# SEG_pressure_gauge_don_V2_3.net
KiCad netlist of a schematic drawn in Altium Designer
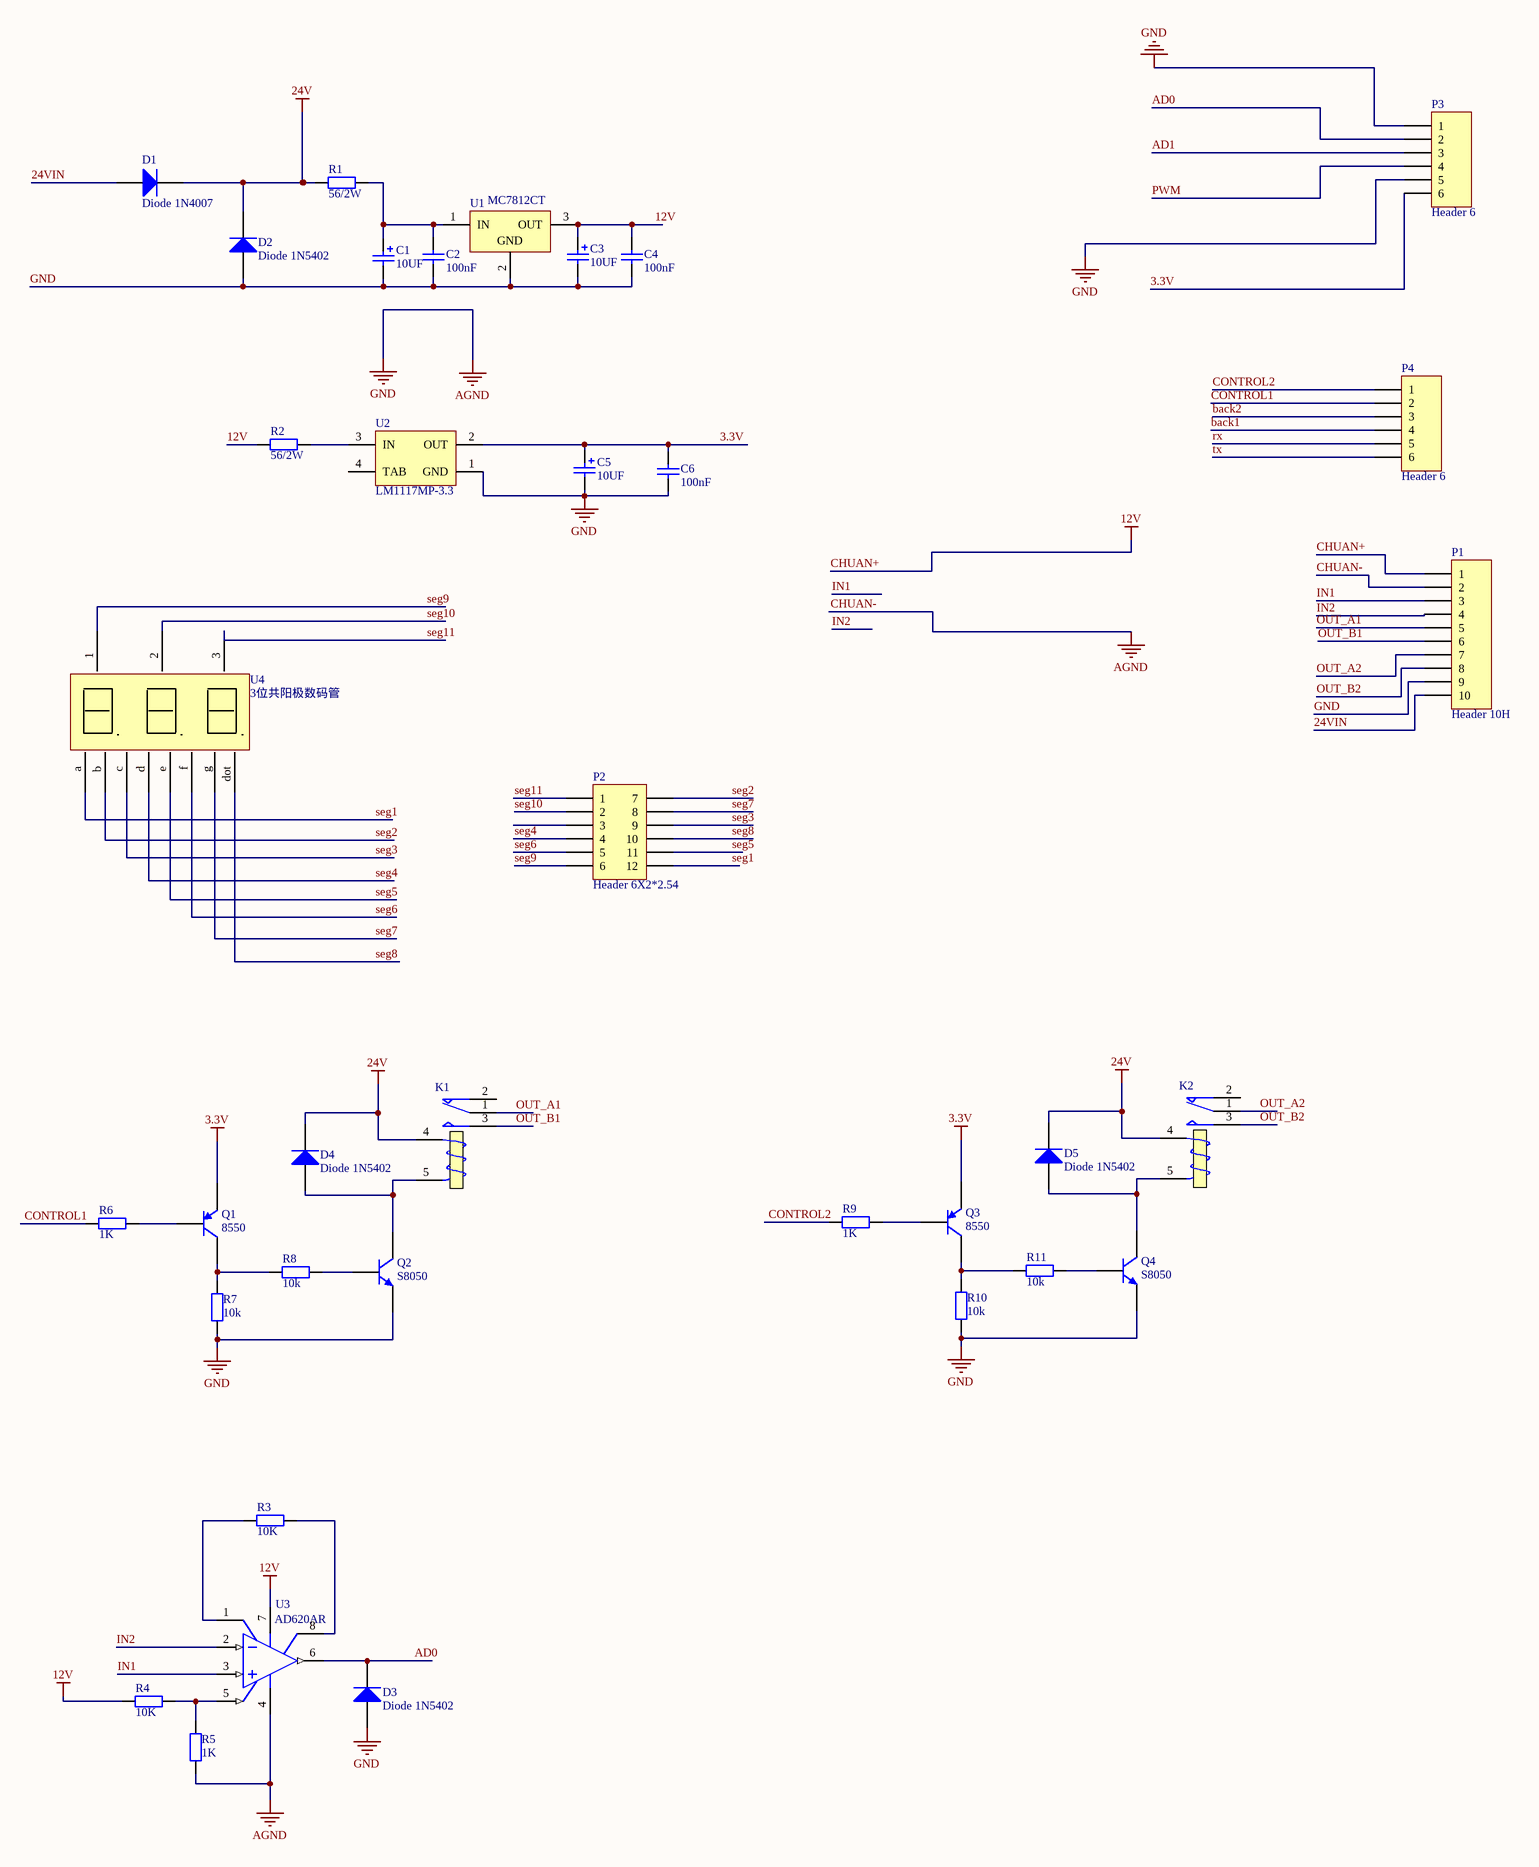
[diagram p0: SEG_pressure gauge_don  V2.3.SchDoc]

(export (version "E")
  (design (tool "Eeschema 10.0.6"))
  (components
    (comp (ref "C1")
      (value "10UF")
      (footprint "3216")
      (description "Polarized Capacitor (Axial)")
      (fields (field (name "Comment") "10uf") (field (name "PUBLISHER") "Altium Limited"))
      (libsource (lib "Miscellaneous Devices") (part "Cap Pol2"))
    )
    (comp (ref "C2")
      (value "100nF")
      (footprint "0805_C_Y")
      (description "Capacitor")
      (fields (field (name "Comment") "100nf") (field (name "PUBLISHER") "Altium Limited"))
      (libsource (lib "Miscellaneous Devices") (part "Cap"))
    )
    (comp (ref "C3")
      (value "10UF")
      (footprint "3216")
      (description "Polarized Capacitor (Axial)")
      (fields (field (name "Comment") "10uf") (field (name "PUBLISHER") "Altium Limited"))
      (libsource (lib "Miscellaneous Devices") (part "Cap Pol2"))
    )
    (comp (ref "C4")
      (value "100nF")
      (footprint "0805_C_Y")
      (description "Capacitor")
      (fields (field (name "Comment") "100nf") (field (name "PUBLISHER") "Altium Limited"))
      (libsource (lib "Miscellaneous Devices") (part "Cap"))
    )
    (comp (ref "C5")
      (value "10UF")
      (footprint "3216")
      (description "Polarized Capacitor (Axial)")
      (fields (field (name "Comment") "10uf") (field (name "PUBLISHER") "Altium Limited"))
      (libsource (lib "Miscellaneous Devices") (part "Cap Pol2"))
    )
    (comp (ref "C6")
      (value "100nF")
      (footprint "0805_C_Y")
      (description "Capacitor")
      (fields (field (name "Comment") "100nf") (field (name "PUBLISHER") "Altium Limited"))
      (libsource (lib "Miscellaneous Devices") (part "Cap"))
    )
    (comp (ref "D1")
      (value "Diode 1N4007")
      (footprint "DO-214")
      (description "1 Amp General Purpose Rectifier")
      (fields (field (name "PUBLISHER") "Altium Limited"))
      (libsource (lib "Miscellaneous Devices") (part "Diode 1N4007"))
    )
    (comp (ref "D2")
      (value "Diode 1N5402")
      (footprint "DO-214")
      (description "3 Amp General Purpose Rectifier")
      (fields (field (name "PUBLISHER") "Altium Limited"))
      (libsource (lib "Miscellaneous Devices") (part "Diode 1N5402"))
    )
    (comp (ref "D3")
      (value "Diode 1N5402")
      (footprint "DO-214")
      (description "3 Amp General Purpose Rectifier")
      (fields (field (name "PUBLISHER") "Altium Limited"))
      (libsource (lib "Miscellaneous Devices") (part "Diode 1N5402"))
    )
    (comp (ref "D4")
      (value "Diode 1N5402")
      (footprint "DO-214")
      (description "3 Amp General Purpose Rectifier")
      (fields (field (name "PUBLISHER") "Altium Limited"))
      (libsource (lib "Miscellaneous Devices") (part "Diode 1N5402"))
    )
    (comp (ref "D5")
      (value "Diode 1N5402")
      (footprint "DO-214")
      (description "3 Amp General Purpose Rectifier")
      (fields (field (name "PUBLISHER") "Altium Limited"))
      (libsource (lib "Miscellaneous Devices") (part "Diode 1N5402"))
    )
    (comp (ref "K1")
      (value "Relay")
      (footprint "HK4100F-DC24V-SHG??")
      (description "SPDT Relay")
      (fields (field (name "PUBLISHER") "Altium Limited"))
      (libsource (lib "Miscellaneous Devices") (part "Relay"))
    )
    (comp (ref "K2")
      (value "Relay")
      (footprint "HK4100F-DC24V-SHG??")
      (description "SPDT Relay")
      (fields (field (name "PUBLISHER") "Altium Limited"))
      (libsource (lib "Miscellaneous Devices") (part "Relay"))
    )
    (comp (ref "P1")
      (value "Header 10H")
      (footprint "HDR1X10H")
      (description "Header, 10-Pin, Right Angle")
      (fields (field (name "PUBLISHER") "Altium Limited"))
      (libsource (lib "Miscellaneous Connectors") (part "Header 10H"))
    )
    (comp (ref "P2")
      (value "Header 6X2*2.54")
      (footprint "HDR2X6_CEN")
      (description "Header, 6-Pin, Dual row")
      (fields (field (name "PUBLISHER") "Altium Limited"))
      (libsource (lib "Miscellaneous Connectors") (part "Header 6X2A"))
    )
    (comp (ref "P3")
      (value "Header 6")
      (footprint "HDR1X6")
      (description "Header, 6-Pin")
      (fields (field (name "PUBLISHER") "Altium Limited"))
      (libsource (lib "Miscellaneous Connectors") (part "Header 6"))
    )
    (comp (ref "P4")
      (value "Header 6")
      (footprint "HDR1X6")
      (description "Header, 6-Pin")
      (fields (field (name "PUBLISHER") "Altium Limited"))
      (libsource (lib "Miscellaneous Connectors") (part "Header 6"))
    )
    (comp (ref "Q1")
      (value "8550")
      (footprint "SOT-23_Y")
      (description "PNP General Purpose Amplifier")
      (fields (field (name "PUBLISHER") "Altium Limited"))
      (libsource (lib "Miscellaneous Devices") (part "2N3906"))
    )
    (comp (ref "Q2")
      (value "S8050")
      (footprint "SOT-23_Y")
      (description "NPN General Purpose Amplifier")
      (fields (field (name "PUBLISHER") "Altium Limited"))
      (libsource (lib "Miscellaneous Devices") (part "2N3904"))
    )
    (comp (ref "Q3")
      (value "8550")
      (footprint "SOT-23_Y")
      (description "PNP General Purpose Amplifier")
      (fields (field (name "PUBLISHER") "Altium Limited"))
      (libsource (lib "Miscellaneous Devices") (part "2N3906"))
    )
    (comp (ref "Q4")
      (value "S8050")
      (footprint "SOT-23_Y")
      (description "NPN General Purpose Amplifier")
      (fields (field (name "PUBLISHER") "Altium Limited"))
      (libsource (lib "Miscellaneous Devices") (part "2N3904"))
    )
    (comp (ref "R1")
      (value "56/2W")
      (footprint "PCBComponent_1 - duplicate")
      (description "Resistor")
      (fields (field (name "PUBLISHER") "Altium Limited"))
      (libsource (lib "") (part "Res2_1"))
    )
    (comp (ref "R2")
      (value "56/2W")
      (footprint "PCBComponent_1 - duplicate")
      (description "Resistor")
      (fields (field (name "PUBLISHER") "Altium Limited"))
      (libsource (lib "") (part "Res2_1"))
    )
    (comp (ref "R3")
      (value "10K")
      (footprint "0805_R_Y")
      (description "Resistor")
      (fields (field (name "Comment") "10k") (field (name "PUBLISHER") "Altium Limited"))
      (libsource (lib "") (part "Res2_1"))
    )
    (comp (ref "R4")
      (value "10K")
      (footprint "0805_R_Y")
      (description "Resistor")
      (fields (field (name "Comment") "10k") (field (name "PUBLISHER") "Altium Limited"))
      (libsource (lib "") (part "Res2_2"))
    )
    (comp (ref "R5")
      (value "1K")
      (footprint "0805_R_Y")
      (description "Resistor")
      (fields (field (name "Comment") "1k") (field (name "PUBLISHER") "Altium Limited"))
      (libsource (lib "Miscellaneous Devices") (part "Res2"))
    )
    (comp (ref "R6")
      (value "1K")
      (footprint "0805_R_Y")
      (description "Resistor")
      (fields (field (name "Comment") "470") (field (name "PUBLISHER") "Altium Limited"))
      (libsource (lib "") (part "Res2_2"))
    )
    (comp (ref "R7")
      (value "10k")
      (footprint "0805_R_Y")
      (description "Resistor")
      (fields (field (name "PUBLISHER") "Altium Limited"))
      (libsource (lib "Miscellaneous Devices") (part "Res2"))
    )
    (comp (ref "R8")
      (value "10k")
      (footprint "0805_R_Y")
      (description "Resistor")
      (fields (field (name "PUBLISHER") "Altium Limited"))
      (libsource (lib "") (part "Res2_2"))
    )
    (comp (ref "R9")
      (value "1K")
      (footprint "0805_R_Y")
      (description "Resistor")
      (fields (field (name "Comment") "470") (field (name "PUBLISHER") "Altium Limited"))
      (libsource (lib "") (part "Res2_2"))
    )
    (comp (ref "R10")
      (value "10k")
      (footprint "0805_R_Y")
      (description "Resistor")
      (fields (field (name "PUBLISHER") "Altium Limited"))
      (libsource (lib "Miscellaneous Devices") (part "Res2"))
    )
    (comp (ref "R11")
      (value "10k")
      (footprint "0805_R_Y")
      (description "Resistor")
      (fields (field (name "PUBLISHER") "Altium Limited"))
      (libsource (lib "") (part "Res2_2"))
    )
    (comp (ref "U1")
      (value "MC7812CT")
      (footprint "TO-220")
      (description "Three-Terminal Positive Voltage Regulator")
      (fields (field (name "PUBLISHER") "Altium Limited"))
      (libsource (lib "ON Semi Power Mgt Voltage Regulator") (part "MC7812CT"))
    )
    (comp (ref "U2")
      (value "LM1117MP-3.3")
      (footprint "MP04A_M")
      (description "800mA Low-Dropout Linear Regulator")
      (fields
        (field (name "MANUFACTURER") "National Semiconductor")
        (field (name "DIGIKEYPARTNUMBER") "LM1117MP-3.3CT-ND")
        (field (name "PUBLISHER") "Altium Limited")
      )
      (libsource (lib "NSC LDO") (part "LM1117MP-3.3"))
    )
    (comp (ref "U3")
      (value "AD620AR")
      (footprint "SO-8_Y")
      (description "Low-Cost, Low-Power Instrumentation Amplifier")
      (fields (field (name "PUBLISHER") "Altium Limited"))
      (libsource (lib "AD Instrumentation Amplifier") (part "AD620AR"))
    )
    (comp (ref "U4") (value "3位共阳极数码管") (footprint "3位数码管0.56") (libsource (lib "kelei") (part "3位共阳极数码管")))
  )
  (nets
    (net (code "1") (name "/24VIN") (class "Default")
      (node (ref "D1") (pin "1") (pinfunction "A_1") (pintype "passive"))
      (node (ref "P1") (pin "10") (pinfunction "10_10") (pintype "passive"))
    )
    (net (code "2") (name "/AD0") (class "Default")
      (node (ref "D3") (pin "2") (pinfunction "K_2") (pintype "passive"))
      (node (ref "P3") (pin "2") (pinfunction "2_2") (pintype "passive"))
      (node (ref "U3") (pin "6") (pinfunction "OUT_6") (pintype "output"))
    )
    (net (code "3") (name "/AD1") (class "Default")
      (node (ref "P3") (pin "3") (pinfunction "3_3") (pintype "passive"))
    )
    (net (code "4") (name "/CONTROL1") (class "Default")
      (node (ref "P4") (pin "2") (pinfunction "2_2") (pintype "passive"))
      (node (ref "R6") (pin "2") (pinfunction "2_2") (pintype "passive"))
    )
    (net (code "5") (name "/CONTROL2") (class "Default")
      (node (ref "P4") (pin "1") (pinfunction "1_1") (pintype "passive"))
      (node (ref "R9") (pin "2") (pinfunction "2_2") (pintype "passive"))
    )
    (net (code "6") (name "/IN1") (class "Default")
      (node (ref "P1") (pin "3") (pinfunction "3_3") (pintype "passive"))
      (node (ref "U3") (pin "3") (pinfunction "+IN_3") (pintype "input"))
    )
    (net (code "7") (name "/IN2") (class "Default")
      (node (ref "P1") (pin "4") (pinfunction "4_4") (pintype "passive"))
      (node (ref "U3") (pin "2") (pinfunction "-IN_2") (pintype "input"))
    )
    (net (code "8") (name "/OUT_A1") (class "Default")
      (node (ref "K1") (pin "1") (pinfunction "COM_1") (pintype "passive"))
      (node (ref "P1") (pin "5") (pinfunction "5_5") (pintype "passive"))
    )
    (net (code "9") (name "/OUT_A2") (class "Default")
      (node (ref "K2") (pin "1") (pinfunction "COM_1") (pintype "passive"))
      (node (ref "P1") (pin "7") (pinfunction "7_7") (pintype "passive"))
    )
    (net (code "10") (name "/OUT_B1") (class "Default")
      (node (ref "K1") (pin "3") (pinfunction "NO_3") (pintype "passive"))
      (node (ref "P1") (pin "6") (pinfunction "6_6") (pintype "passive"))
    )
    (net (code "11") (name "/OUT_B2") (class "Default")
      (node (ref "K2") (pin "3") (pinfunction "NO_3") (pintype "passive"))
      (node (ref "P1") (pin "8") (pinfunction "8_8") (pintype "passive"))
    )
    (net (code "12") (name "/PWM") (class "Default")
      (node (ref "P3") (pin "4") (pinfunction "4_4") (pintype "passive"))
    )
    (net (code "13") (name "/back1") (class "Default")
      (node (ref "P4") (pin "4") (pinfunction "4_4") (pintype "passive"))
    )
    (net (code "14") (name "/back2") (class "Default")
      (node (ref "P4") (pin "3") (pinfunction "3_3") (pintype "passive"))
    )
    (net (code "15") (name "/rx") (class "Default")
      (node (ref "P4") (pin "5") (pinfunction "5_5") (pintype "passive"))
    )
    (net (code "16") (name "/seg1") (class "Default")
      (node (ref "P2") (pin "12") (pinfunction "12_12") (pintype "passive"))
      (node (ref "U4") (pin "a") (pinfunction "a_a") (pintype "passive"))
    )
    (net (code "17") (name "/seg2") (class "Default")
      (node (ref "P2") (pin "7") (pinfunction "7_7") (pintype "passive"))
      (node (ref "U4") (pin "b") (pinfunction "b_b") (pintype "passive"))
    )
    (net (code "18") (name "/seg3") (class "Default")
      (node (ref "P2") (pin "9") (pinfunction "9_9") (pintype "passive"))
      (node (ref "U4") (pin "c") (pinfunction "c_c") (pintype "passive"))
    )
    (net (code "19") (name "/seg4") (class "Default")
      (node (ref "P2") (pin "4") (pinfunction "4_4") (pintype "passive"))
      (node (ref "U4") (pin "d") (pinfunction "d_d") (pintype "passive"))
    )
    (net (code "20") (name "/seg5") (class "Default")
      (node (ref "P2") (pin "11") (pinfunction "11_11") (pintype "passive"))
      (node (ref "U4") (pin "e") (pinfunction "e_e") (pintype "passive"))
    )
    (net (code "21") (name "/seg6") (class "Default")
      (node (ref "P2") (pin "5") (pinfunction "5_5") (pintype "passive"))
      (node (ref "U4") (pin "f") (pinfunction "f_f") (pintype "passive"))
    )
    (net (code "22") (name "/seg7") (class "Default")
      (node (ref "P2") (pin "8") (pinfunction "8_8") (pintype "passive"))
      (node (ref "U4") (pin "g") (pinfunction "g_g") (pintype "passive"))
    )
    (net (code "23") (name "/seg8") (class "Default")
      (node (ref "P2") (pin "10") (pinfunction "10_10") (pintype "passive"))
      (node (ref "U4") (pin "dot") (pinfunction "dot_dot") (pintype "passive"))
    )
    (net (code "24") (name "/seg9") (class "Default")
      (node (ref "P2") (pin "6") (pinfunction "6_6") (pintype "passive"))
      (node (ref "U4") (pin "1") (pinfunction "1_1") (pintype "passive"))
    )
    (net (code "25") (name "/seg10") (class "Default")
      (node (ref "P2") (pin "2") (pinfunction "2_2") (pintype "passive"))
      (node (ref "U4") (pin "2") (pinfunction "2_2") (pintype "passive"))
    )
    (net (code "26") (name "/seg11") (class "Default")
      (node (ref "P2") (pin "1") (pinfunction "1_1") (pintype "passive"))
      (node (ref "U4") (pin "3") (pinfunction "3_3") (pintype "passive"))
    )
    (net (code "27") (name "/tx") (class "Default")
      (node (ref "P4") (pin "6") (pinfunction "6_6") (pintype "passive"))
    )
    (net (code "28") (name "3.3V") (class "Default")
      (node (ref "C5") (pin "1") (pinfunction "1_1") (pintype "passive"))
      (node (ref "C6") (pin "1") (pinfunction "1_1") (pintype "passive"))
      (node (ref "P3") (pin "6") (pinfunction "6_6") (pintype "passive"))
      (node (ref "Q1") (pin "2") (pinfunction "E_2") (pintype "passive"))
      (node (ref "Q3") (pin "2") (pinfunction "E_2") (pintype "passive"))
      (node (ref "U2") (pin "2") (pinfunction "OUT_2") (pintype "power_in"))
    )
    (net (code "29") (name "12V") (class "Default")
      (node (ref "C3") (pin "1") (pinfunction "1_1") (pintype "passive"))
      (node (ref "C4") (pin "1") (pinfunction "1_1") (pintype "passive"))
      (node (ref "P1") (pin "1") (pinfunction "1_1") (pintype "passive"))
      (node (ref "R2") (pin "1") (pinfunction "1_1") (pintype "passive"))
      (node (ref "R4") (pin "2") (pinfunction "2_2") (pintype "passive"))
      (node (ref "U1") (pin "3") (pinfunction "OUT_3") (pintype "power_in"))
      (node (ref "U3") (pin "7") (pinfunction "V+_7") (pintype "power_in"))
    )
    (net (code "30") (name "24V") (class "Default")
      (node (ref "D1") (pin "2") (pinfunction "K_2") (pintype "passive"))
      (node (ref "D2") (pin "2") (pinfunction "K_2") (pintype "passive"))
      (node (ref "D4") (pin "2") (pinfunction "K_2") (pintype "passive"))
      (node (ref "D5") (pin "2") (pinfunction "K_2") (pintype "passive"))
      (node (ref "K1") (pin "4") (pinfunction "T1_4") (pintype "passive"))
      (node (ref "K2") (pin "4") (pinfunction "T1_4") (pintype "passive"))
      (node (ref "R1") (pin "1") (pinfunction "1_1") (pintype "passive"))
    )
    (net (code "31") (name "AGND") (class "Default")
      (node (ref "C1") (pin "2") (pinfunction "2_2") (pintype "passive"))
      (node (ref "C2") (pin "2") (pinfunction "2_2") (pintype "passive"))
      (node (ref "C3") (pin "2") (pinfunction "2_2") (pintype "passive"))
      (node (ref "C4") (pin "2") (pinfunction "2_2") (pintype "passive"))
      (node (ref "C5") (pin "2") (pinfunction "2_2") (pintype "passive"))
      (node (ref "C6") (pin "2") (pinfunction "2_2") (pintype "passive"))
      (node (ref "D2") (pin "1") (pinfunction "A_1") (pintype "passive"))
      (node (ref "D3") (pin "1") (pinfunction "A_1") (pintype "passive"))
      (node (ref "P1") (pin "2") (pinfunction "2_2") (pintype "passive"))
      (node (ref "P1") (pin "9") (pinfunction "9_9") (pintype "passive"))
      (node (ref "P3") (pin "1") (pinfunction "1_1") (pintype "passive"))
      (node (ref "P3") (pin "5") (pinfunction "5_5") (pintype "passive"))
      (node (ref "Q2") (pin "2") (pinfunction "E_2") (pintype "passive"))
      (node (ref "Q4") (pin "2") (pinfunction "E_2") (pintype "passive"))
      (node (ref "R10") (pin "1") (pinfunction "1_1") (pintype "passive"))
      (node (ref "R5") (pin "1") (pinfunction "1_1") (pintype "passive"))
      (node (ref "R7") (pin "1") (pinfunction "1_1") (pintype "passive"))
      (node (ref "U1") (pin "2") (pinfunction "GND_2") (pintype "power_in"))
      (node (ref "U2") (pin "1") (pinfunction "GND_1") (pintype "power_in"))
      (node (ref "U3") (pin "4") (pinfunction "V-_4") (pintype "power_in"))
    )
    (net (code "32") (name "Net-(D4-A)") (class "Default")
      (node (ref "D4") (pin "1") (pinfunction "A_1") (pintype "passive"))
      (node (ref "K1") (pin "5") (pinfunction "T2_5") (pintype "passive"))
      (node (ref "Q2") (pin "3") (pinfunction "C_3") (pintype "passive"))
    )
    (net (code "33") (name "Net-(D5-A)") (class "Default")
      (node (ref "D5") (pin "1") (pinfunction "A_1") (pintype "passive"))
      (node (ref "K2") (pin "5") (pinfunction "T2_5") (pintype "passive"))
      (node (ref "Q4") (pin "3") (pinfunction "C_3") (pintype "passive"))
    )
    (net (code "34") (name "Net-(Q1-B)") (class "Default")
      (node (ref "Q1") (pin "1") (pinfunction "B_1") (pintype "passive"))
      (node (ref "R6") (pin "1") (pinfunction "1_1") (pintype "passive"))
    )
    (net (code "35") (name "Net-(Q1-C)") (class "Default")
      (node (ref "Q1") (pin "3") (pinfunction "C_3") (pintype "passive"))
      (node (ref "R7") (pin "2") (pinfunction "2_2") (pintype "passive"))
      (node (ref "R8") (pin "2") (pinfunction "2_2") (pintype "passive"))
    )
    (net (code "36") (name "Net-(Q2-B)") (class "Default")
      (node (ref "Q2") (pin "1") (pinfunction "B_1") (pintype "passive"))
      (node (ref "R8") (pin "1") (pinfunction "1_1") (pintype "passive"))
    )
    (net (code "37") (name "Net-(Q3-B)") (class "Default")
      (node (ref "Q3") (pin "1") (pinfunction "B_1") (pintype "passive"))
      (node (ref "R9") (pin "1") (pinfunction "1_1") (pintype "passive"))
    )
    (net (code "38") (name "Net-(Q3-C)") (class "Default")
      (node (ref "Q3") (pin "3") (pinfunction "C_3") (pintype "passive"))
      (node (ref "R10") (pin "2") (pinfunction "2_2") (pintype "passive"))
      (node (ref "R11") (pin "2") (pinfunction "2_2") (pintype "passive"))
    )
    (net (code "39") (name "Net-(Q4-B)") (class "Default")
      (node (ref "Q4") (pin "1") (pinfunction "B_1") (pintype "passive"))
      (node (ref "R11") (pin "1") (pinfunction "1_1") (pintype "passive"))
    )
    (net (code "40") (name "Net-(R3-Pad1)") (class "Default")
      (node (ref "R3") (pin "1") (pinfunction "1_1") (pintype "passive"))
      (node (ref "U3") (pin "1") (pinfunction "RG_1") (pintype "passive"))
    )
    (net (code "41") (name "Net-(R3-Pad2)") (class "Default")
      (node (ref "R3") (pin "2") (pinfunction "2_2") (pintype "passive"))
      (node (ref "U3") (pin "8") (pinfunction "RG_8") (pintype "passive"))
    )
    (net (code "42") (name "Net-(U1-IN)") (class "Default")
      (node (ref "C1") (pin "1") (pinfunction "1_1") (pintype "passive"))
      (node (ref "C2") (pin "1") (pinfunction "1_1") (pintype "passive"))
      (node (ref "R1") (pin "2") (pinfunction "2_2") (pintype "passive"))
      (node (ref "U1") (pin "1") (pinfunction "IN_1") (pintype "power_in"))
    )
    (net (code "43") (name "Net-(U2-IN)") (class "Default")
      (node (ref "R2") (pin "2") (pinfunction "2_2") (pintype "passive"))
      (node (ref "U2") (pin "3") (pinfunction "IN_3") (pintype "power_in"))
    )
    (net (code "44") (name "Net-(U3-REF)") (class "Default")
      (node (ref "R4") (pin "1") (pinfunction "1_1") (pintype "passive"))
      (node (ref "R5") (pin "2") (pinfunction "2_2") (pintype "passive"))
      (node (ref "U3") (pin "5") (pinfunction "REF_5") (pintype "input"))
    )
    (net (code "45") (name "unconnected-(K1-NC-Pad2)") (class "Default")
      (node (ref "K1") (pin "2") (pinfunction "NC_2") (pintype "passive"))
    )
    (net (code "46") (name "unconnected-(K2-NC-Pad2)") (class "Default")
      (node (ref "K2") (pin "2") (pinfunction "NC_2") (pintype "passive"))
    )
    (net (code "47") (name "unconnected-(P2-Pad3)") (class "Default")
      (node (ref "P2") (pin "3") (pinfunction "3_3") (pintype "passive"))
    )
    (net (code "48") (name "unconnected-(U2-TAB-Pad4)") (class "Default")
      (node (ref "U2") (pin "4") (pinfunction "TAB_4") (pintype "power_in"))
    )
  )
)
